# EEPROM.net
KiCad netlist of a schematic drawn in Altium Designer
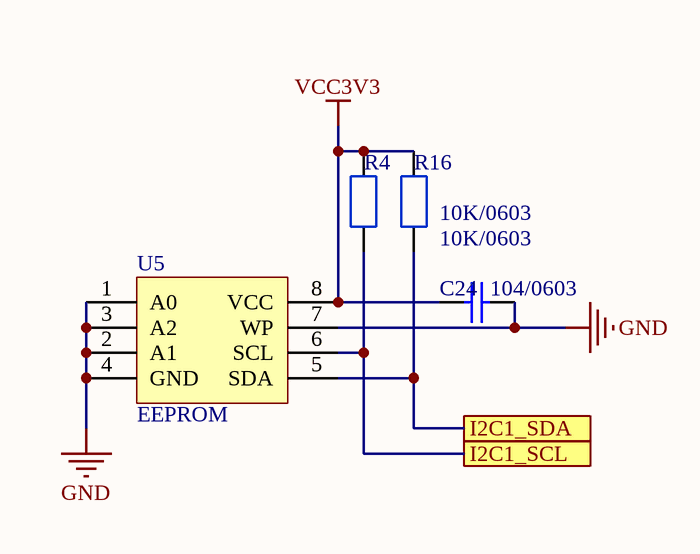
[diagram p0: EEPROM.SchDoc]

(export (version "E")
  (design (tool "Eeschema 10.0.6"))
  (components
    (comp (ref "C24")
      (value "104/0603")
      (footprint "C0603")
      (description "无极性贴片电容")
      (libsource (lib "常用原件") (part "CAP"))
    )
    (comp (ref "R4") (value "10K/0603") (footprint "R0603") (libsource (lib "常用原件") (part "RES")))
    (comp (ref "R16") (value "10K/0603") (footprint "R0603") (libsource (lib "常用原件") (part "RES")))
    (comp (ref "U5") (value "EEPROM") (footprint "SOP8") (libsource (lib "常用原件") (part "24CXX")))
  )
  (nets
    (net (code "1") (name "/I2C1_SCL") (class "Default")
      (node (ref "R4") (pin "1") (pinfunction "1_1") (pintype "passive"))
      (node (ref "U5") (pin "6") (pinfunction "SCL_6") (pintype "passive"))
    )
    (net (code "2") (name "/I2C1_SDA") (class "Default")
      (node (ref "R16") (pin "1") (pinfunction "1_1") (pintype "passive"))
      (node (ref "U5") (pin "5") (pinfunction "SDA_5") (pintype "passive"))
    )
    (net (code "3") (name "GND") (class "Default")
      (node (ref "C24") (pin "2") (pinfunction "2_2") (pintype "passive"))
      (node (ref "U5") (pin "1") (pinfunction "A0_1") (pintype "passive"))
      (node (ref "U5") (pin "2") (pinfunction "A1_2") (pintype "passive"))
      (node (ref "U5") (pin "3") (pinfunction "A2_3") (pintype "passive"))
      (node (ref "U5") (pin "4") (pinfunction "GND_4") (pintype "passive"))
      (node (ref "U5") (pin "7") (pinfunction "WP_7") (pintype "passive"))
    )
    (net (code "4") (name "VCC3V3") (class "Default")
      (node (ref "C24") (pin "1") (pinfunction "1_1") (pintype "passive"))
      (node (ref "R16") (pin "2") (pinfunction "2_2") (pintype "passive"))
      (node (ref "R4") (pin "2") (pinfunction "2_2") (pintype "passive"))
      (node (ref "U5") (pin "8") (pinfunction "VCC_8") (pintype "passive"))
    )
  )
)
